# SCH_sign-language-translation-glove_2025.net
KiCad netlist of a schematic drawn in EasyEDA
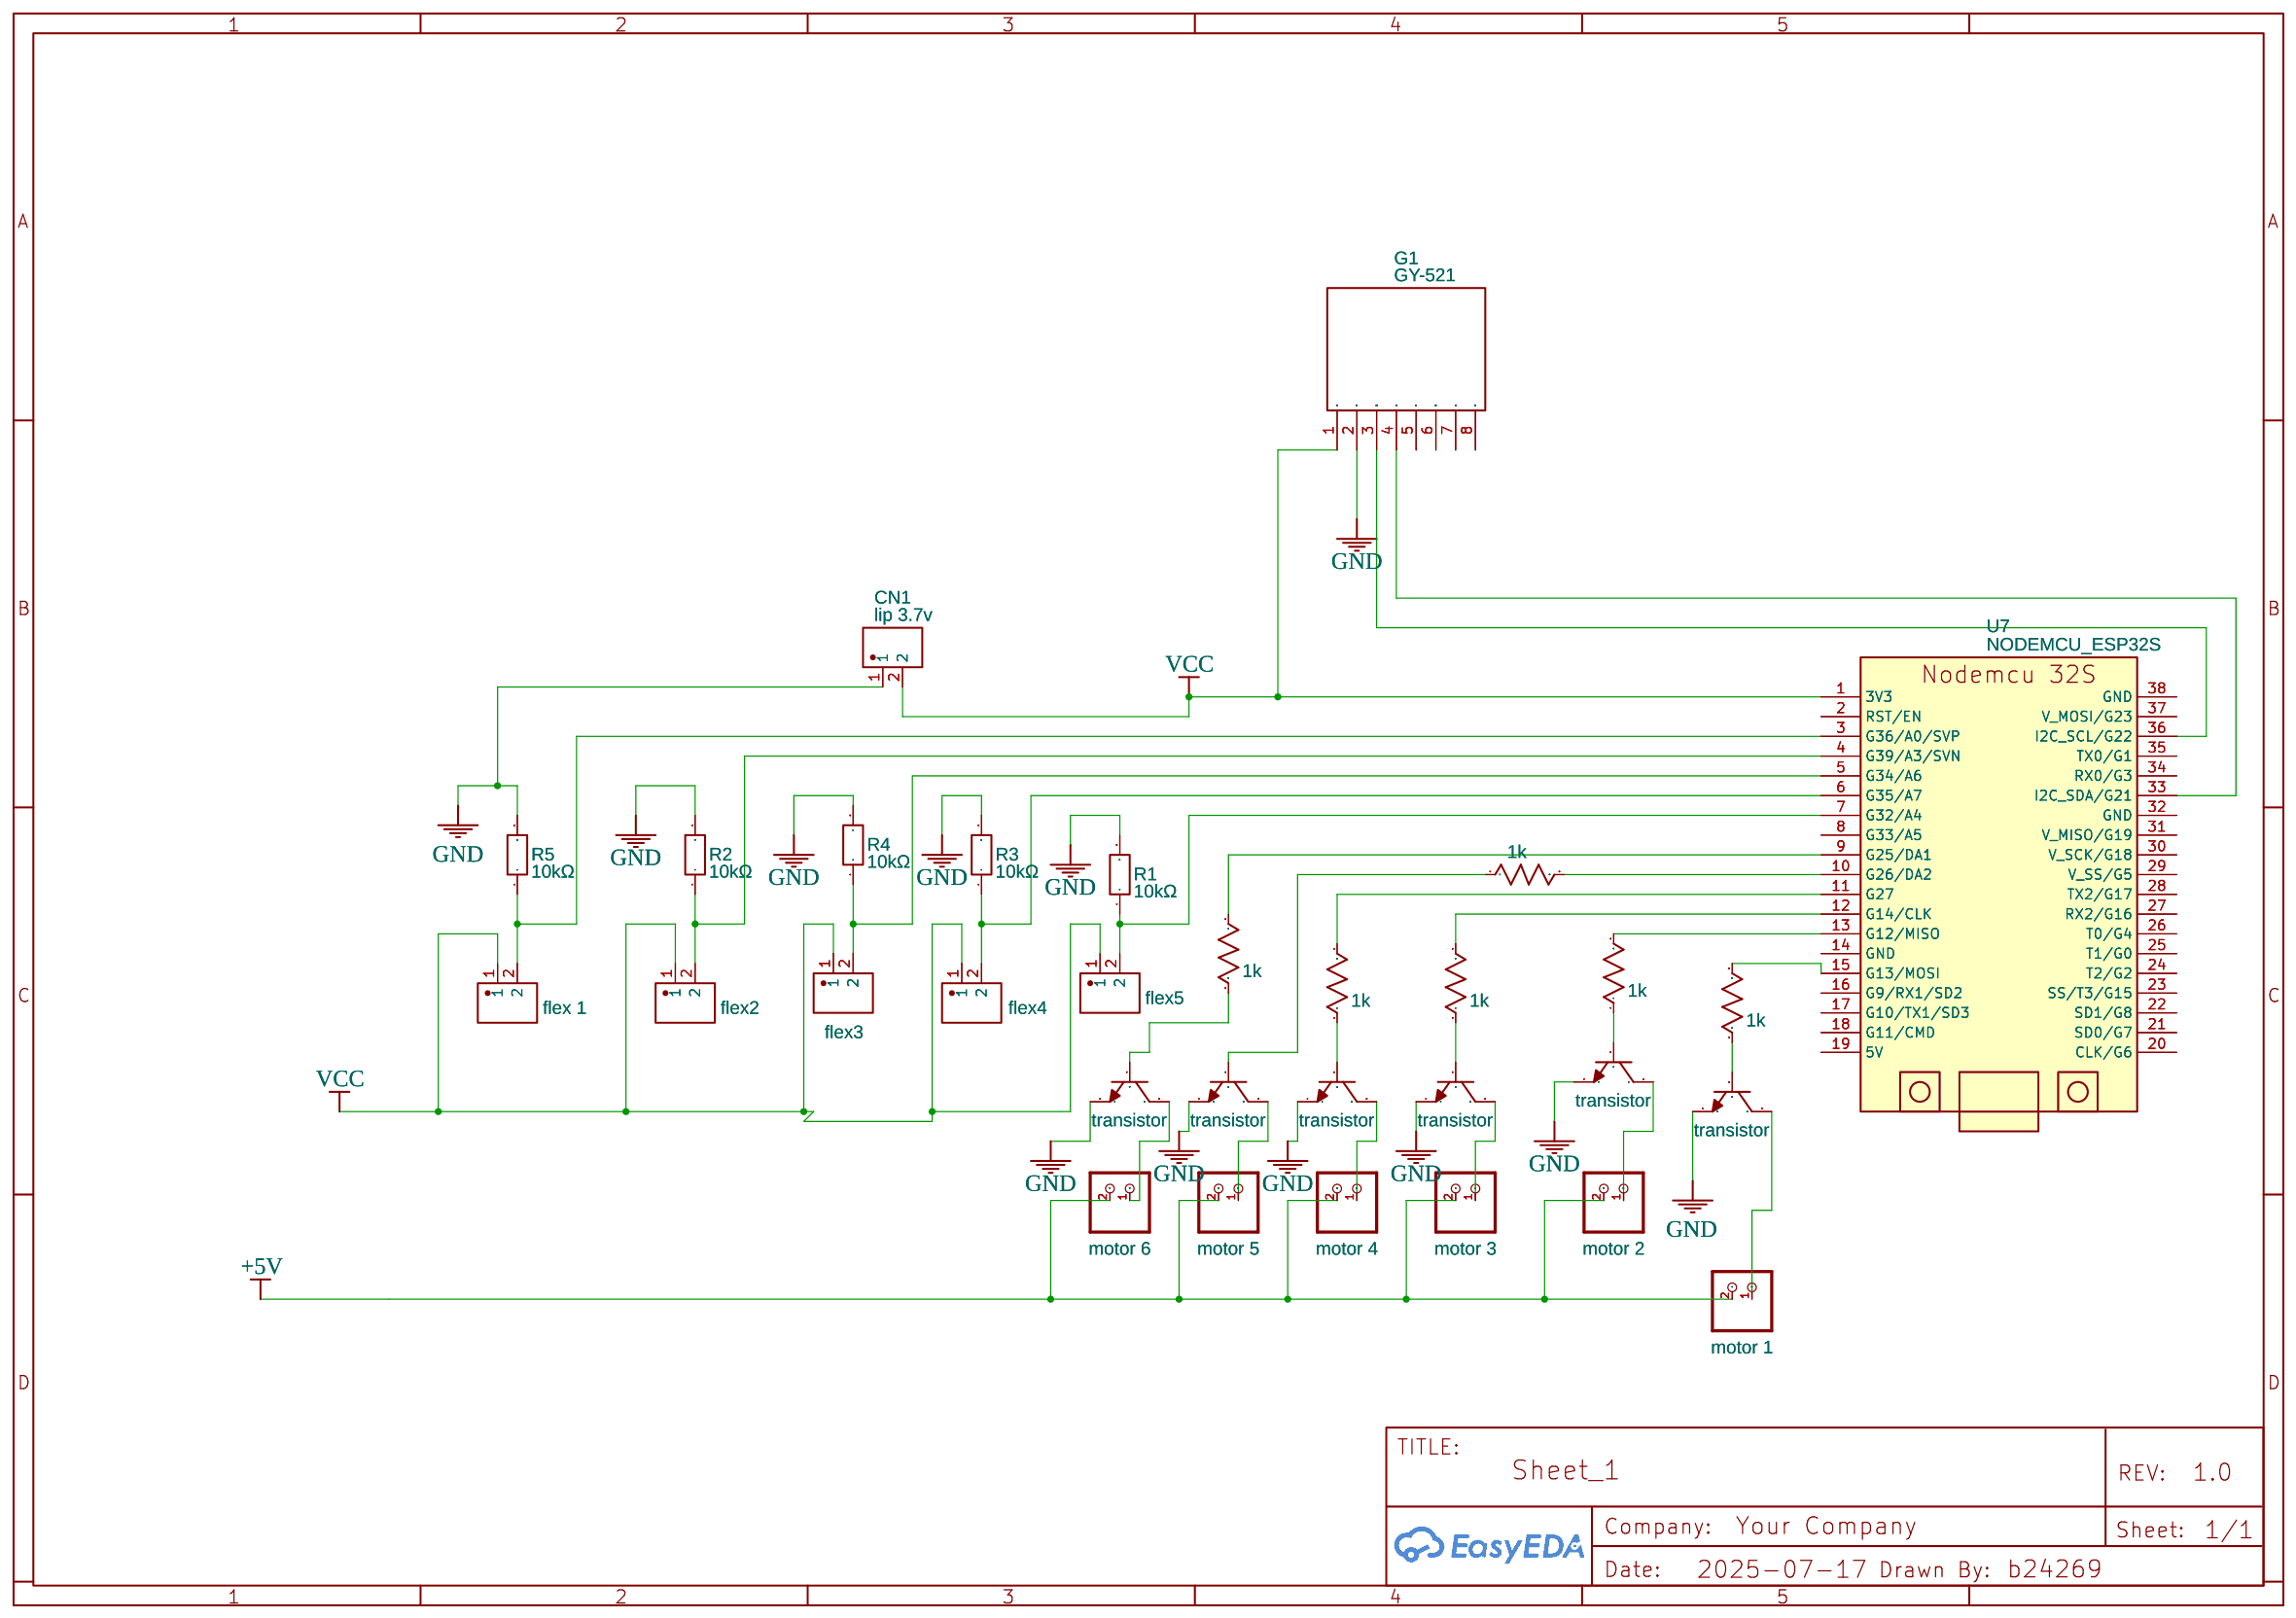
[diagram p0: schematic sheet]

(export (version "E")
  (design (tool "Eeschema 10.0.6"))
  (components
    (comp (ref "CN1")
      (value "lip 3.7v")
      (fields
        (field (name "Manufacturer Part") "2.0-2P ZZDK-R PCB Connector")
        (field (name "Manufacturer") "SHOU HAN(首韩)")
      )
      (libsource (lib "") (part "2.0-2P ZZDK-R PCB CONNECTOR"))
    )
    (comp (ref "CN2") (value "motor 1") (libsource (lib "") (part "JST_2PIN-THM")))
    (comp (ref "CN3") (value "motor 2") (libsource (lib "") (part "JST_2PIN-THM")))
    (comp (ref "CN4") (value "motor 3") (libsource (lib "") (part "JST_2PIN-THM")))
    (comp (ref "CN5") (value "motor 4") (libsource (lib "") (part "JST_2PIN-THM")))
    (comp (ref "CN6") (value "motor 5") (libsource (lib "") (part "JST_2PIN-THM")))
    (comp (ref "CN7") (value "motor 6") (libsource (lib "") (part "JST_2PIN-THM")))
    (comp (ref "G1") (value "GY-521") (libsource (lib "") (part "GY-521")))
    (comp (ref "Q1")
      (value "transistor")
      (fields (field (name "Manufacturer Part") "2n3904S-RTK/PS") (field (name "Manufacturer") "KEC"))
      (libsource (lib "") (part "2N3904(SOT-23)"))
    )
    (comp (ref "Q2")
      (value "transistor")
      (fields (field (name "Manufacturer Part") "2n3904S-RTK/PS") (field (name "Manufacturer") "KEC"))
      (libsource (lib "") (part "2N3904(SOT-23)"))
    )
    (comp (ref "Q3")
      (value "transistor")
      (fields (field (name "Manufacturer Part") "2n3904S-RTK/PS") (field (name "Manufacturer") "KEC"))
      (libsource (lib "") (part "2N3904(SOT-23)"))
    )
    (comp (ref "Q4")
      (value "transistor")
      (fields (field (name "Manufacturer Part") "2n3904S-RTK/PS") (field (name "Manufacturer") "KEC"))
      (libsource (lib "") (part "2N3904(SOT-23)"))
    )
    (comp (ref "Q5")
      (value "transistor")
      (fields (field (name "Manufacturer Part") "2n3904S-RTK/PS") (field (name "Manufacturer") "KEC"))
      (libsource (lib "") (part "2N3904(SOT-23)"))
    )
    (comp (ref "Q6")
      (value "transistor")
      (fields (field (name "Manufacturer Part") "2n3904S-RTK/PS") (field (name "Manufacturer") "KEC"))
      (libsource (lib "") (part "2N3904(SOT-23)"))
    )
    (comp (ref "R1")
      (value "10kΩ")
      (fields (field (name "Manufacturer Part") "APC0805T10K0Z") (field (name "Manufacturer") "Ohmite"))
      (libsource (lib "") (part "APC0805T10K0Z"))
    )
    (comp (ref "R2")
      (value "10kΩ")
      (fields (field (name "Manufacturer Part") "APC0805T10K0Z") (field (name "Manufacturer") "Ohmite"))
      (libsource (lib "") (part "APC0805T10K0Z"))
    )
    (comp (ref "R3")
      (value "10kΩ")
      (fields (field (name "Manufacturer Part") "APC0805T10K0Z") (field (name "Manufacturer") "Ohmite"))
      (libsource (lib "") (part "APC0805T10K0Z"))
    )
    (comp (ref "R4")
      (value "10kΩ")
      (fields (field (name "Manufacturer Part") "APC0805T10K0Z") (field (name "Manufacturer") "Ohmite"))
      (libsource (lib "") (part "APC0805T10K0Z"))
    )
    (comp (ref "R5")
      (value "10kΩ")
      (fields (field (name "Manufacturer Part") "APC0805T10K0Z") (field (name "Manufacturer") "Ohmite"))
      (libsource (lib "") (part "APC0805T10K0Z"))
    )
    (comp (ref "R6") (value "1k") (libsource (lib "") (part "R_0805_US")))
    (comp (ref "R7") (value "1k") (libsource (lib "") (part "R_0805_US")))
    (comp (ref "R8") (value "1k") (libsource (lib "") (part "R_0805_US")))
    (comp (ref "R9") (value "1k") (libsource (lib "") (part "R_0805_US")))
    (comp (ref "R10") (value "1k") (libsource (lib "") (part "R_0805_US_2")))
    (comp (ref "R11") (value "1k") (libsource (lib "") (part "R_0805_US_1")))
    (comp (ref "U1")
      (value "flex5")
      (fields
        (field (name "Manufacturer Part") "5BML8-11732-102-W0")
        (field (name "Manufacturer") "SAMZO(三佐)")
      )
      (libsource (lib "") (part "5BML8-11732-102-W0"))
    )
    (comp (ref "U2")
      (value "flex 1")
      (fields
        (field (name "Manufacturer Part") "5BML8-11732-102-W0")
        (field (name "Manufacturer") "SAMZO(三佐)")
      )
      (libsource (lib "") (part "5BML8-11732-102-W0"))
    )
    (comp (ref "U3")
      (value "flex2")
      (fields
        (field (name "Manufacturer Part") "5BML8-11732-102-W0")
        (field (name "Manufacturer") "SAMZO(三佐)")
      )
      (libsource (lib "") (part "5BML8-11732-102-W0"))
    )
    (comp (ref "U4")
      (value "flex3")
      (fields
        (field (name "Manufacturer Part") "5BML8-11732-102-W0")
        (field (name "Manufacturer") "SAMZO(三佐)")
      )
      (libsource (lib "") (part "5BML8-11732-102-W0"))
    )
    (comp (ref "U5")
      (value "flex4")
      (fields
        (field (name "Manufacturer Part") "5BML8-11732-102-W0")
        (field (name "Manufacturer") "SAMZO(三佐)")
      )
      (libsource (lib "") (part "5BML8-11732-102-W0"))
    )
    (comp (ref "U7")
      (value "NODEMCU_ESP32S")
      (fields (field (name "Manufacturer Part") "Nodemcu esp32"))
      (libsource (lib "") (part "NODEMCU_ESP32S"))
    )
  )
  (nets
    (net (code "1") (name "+5V") (class "Default")
      (node (ref "CN2") (pin "2") (pinfunction "1_2") (pintype "bidirectional"))
      (node (ref "CN3") (pin "2") (pinfunction "1_2") (pintype "bidirectional"))
      (node (ref "CN4") (pin "2") (pinfunction "1_2") (pintype "bidirectional"))
      (node (ref "CN5") (pin "2") (pinfunction "1_2") (pintype "bidirectional"))
      (node (ref "CN6") (pin "2") (pinfunction "1_2") (pintype "bidirectional"))
      (node (ref "CN7") (pin "2") (pinfunction "1_2") (pintype "bidirectional"))
    )
    (net (code "2") (name "GND") (class "Default")
      (node (ref "CN1") (pin "1") (pinfunction "1_1") (pintype "unspecified"))
      (node (ref "G1") (pin "2") (pinfunction "GND_2") (pintype "unspecified"))
      (node (ref "Q1") (pin "1") (pinfunction "E_1") (pintype "input"))
      (node (ref "Q2") (pin "1") (pinfunction "E_1") (pintype "input"))
      (node (ref "Q3") (pin "1") (pinfunction "E_1") (pintype "input"))
      (node (ref "Q4") (pin "1") (pinfunction "E_1") (pintype "input"))
      (node (ref "Q5") (pin "1") (pinfunction "E_1") (pintype "input"))
      (node (ref "Q6") (pin "1") (pinfunction "E_1") (pintype "input"))
      (node (ref "R1") (pin "2") (pinfunction "2_2") (pintype "unspecified"))
      (node (ref "R2") (pin "2") (pinfunction "2_2") (pintype "unspecified"))
      (node (ref "R3") (pin "2") (pinfunction "2_2") (pintype "unspecified"))
      (node (ref "R4") (pin "2") (pinfunction "2_2") (pintype "unspecified"))
      (node (ref "R5") (pin "2") (pinfunction "2_2") (pintype "unspecified"))
    )
    (net (code "3") (name "Net-(CN2-2)") (class "Default")
      (node (ref "CN2") (pin "1") (pinfunction "2_1") (pintype "bidirectional"))
      (node (ref "Q1") (pin "3") (pinfunction "C_3") (pintype "input"))
    )
    (net (code "4") (name "Net-(CN3-2)") (class "Default")
      (node (ref "CN3") (pin "1") (pinfunction "2_1") (pintype "bidirectional"))
      (node (ref "Q2") (pin "3") (pinfunction "C_3") (pintype "input"))
    )
    (net (code "5") (name "Net-(CN4-2)") (class "Default")
      (node (ref "CN4") (pin "1") (pinfunction "2_1") (pintype "bidirectional"))
      (node (ref "Q3") (pin "3") (pinfunction "C_3") (pintype "input"))
    )
    (net (code "6") (name "Net-(CN5-2)") (class "Default")
      (node (ref "CN5") (pin "1") (pinfunction "2_1") (pintype "bidirectional"))
      (node (ref "Q4") (pin "3") (pinfunction "C_3") (pintype "input"))
    )
    (net (code "7") (name "Net-(CN6-2)") (class "Default")
      (node (ref "CN6") (pin "1") (pinfunction "2_1") (pintype "bidirectional"))
      (node (ref "Q5") (pin "3") (pinfunction "C_3") (pintype "input"))
    )
    (net (code "8") (name "Net-(CN7-2)") (class "Default")
      (node (ref "CN7") (pin "1") (pinfunction "2_1") (pintype "bidirectional"))
      (node (ref "Q6") (pin "3") (pinfunction "C_3") (pintype "input"))
    )
    (net (code "9") (name "Net-(G1-SCL)") (class "Default")
      (node (ref "G1") (pin "3") (pinfunction "SCL_3") (pintype "unspecified"))
      (node (ref "U7") (pin "36") (pinfunction "I2C_SCL/G22_36") (pintype "bidirectional"))
    )
    (net (code "10") (name "Net-(G1-SDA)") (class "Default")
      (node (ref "G1") (pin "4") (pinfunction "SDA_4") (pintype "unspecified"))
      (node (ref "U7") (pin "33") (pinfunction "I2C_SDA/G21_33") (pintype "bidirectional"))
    )
    (net (code "11") (name "Net-(Q1-B)") (class "Default")
      (node (ref "Q1") (pin "2") (pinfunction "B_2") (pintype "input"))
      (node (ref "R6") (pin "1") (pinfunction "1_1") (pintype "unspecified"))
    )
    (net (code "12") (name "Net-(Q2-B)") (class "Default")
      (node (ref "Q2") (pin "2") (pinfunction "B_2") (pintype "input"))
      (node (ref "R7") (pin "1") (pinfunction "1_1") (pintype "unspecified"))
    )
    (net (code "13") (name "Net-(Q3-B)") (class "Default")
      (node (ref "Q3") (pin "2") (pinfunction "B_2") (pintype "input"))
      (node (ref "R8") (pin "1") (pinfunction "1_1") (pintype "unspecified"))
    )
    (net (code "14") (name "Net-(Q4-B)") (class "Default")
      (node (ref "Q4") (pin "2") (pinfunction "B_2") (pintype "input"))
      (node (ref "R9") (pin "1") (pinfunction "1_1") (pintype "unspecified"))
    )
    (net (code "15") (name "Net-(Q5-B)") (class "Default")
      (node (ref "Q5") (pin "2") (pinfunction "B_2") (pintype "input"))
      (node (ref "R10") (pin "1") (pinfunction "1_1") (pintype "unspecified"))
    )
    (net (code "16") (name "Net-(Q6-B)") (class "Default")
      (node (ref "Q6") (pin "2") (pinfunction "B_2") (pintype "input"))
      (node (ref "R11") (pin "2") (pinfunction "2_2") (pintype "unspecified"))
    )
    (net (code "17") (name "Net-(U7-G12{slash}MISO)") (class "Default")
      (node (ref "R7") (pin "2") (pinfunction "2_2") (pintype "unspecified"))
      (node (ref "U7") (pin "13") (pinfunction "G12/MISO_13") (pintype "bidirectional"))
    )
    (net (code "18") (name "Net-(U7-G13{slash}MOSI)") (class "Default")
      (node (ref "R6") (pin "2") (pinfunction "2_2") (pintype "unspecified"))
      (node (ref "U7") (pin "15") (pinfunction "G13/MOSI_15") (pintype "bidirectional"))
    )
    (net (code "19") (name "Net-(U7-G14{slash}CLK)") (class "Default")
      (node (ref "R8") (pin "2") (pinfunction "2_2") (pintype "unspecified"))
      (node (ref "U7") (pin "12") (pinfunction "G14/CLK_12") (pintype "bidirectional"))
    )
    (net (code "20") (name "Net-(U7-G25{slash}DA1)") (class "Default")
      (node (ref "R11") (pin "1") (pinfunction "1_1") (pintype "unspecified"))
      (node (ref "U7") (pin "9") (pinfunction "G25/DA1_9") (pintype "bidirectional"))
    )
    (net (code "21") (name "Net-(U7-G26{slash}DA2)") (class "Default")
      (node (ref "R10") (pin "2") (pinfunction "2_2") (pintype "unspecified"))
      (node (ref "U7") (pin "10") (pinfunction "G26/DA2_10") (pintype "bidirectional"))
    )
    (net (code "22") (name "Net-(U7-G27)") (class "Default")
      (node (ref "R9") (pin "2") (pinfunction "2_2") (pintype "unspecified"))
      (node (ref "U7") (pin "11") (pinfunction "G27_11") (pintype "bidirectional"))
    )
    (net (code "23") (name "Net-(U7-G32{slash}A4)") (class "Default")
      (node (ref "R1") (pin "1") (pinfunction "1_1") (pintype "unspecified"))
      (node (ref "U1") (pin "2") (pinfunction "2_2") (pintype "unspecified"))
      (node (ref "U7") (pin "7") (pinfunction "G32/A4_7") (pintype "bidirectional"))
    )
    (net (code "24") (name "Net-(U7-G34{slash}A6)") (class "Default")
      (node (ref "R4") (pin "1") (pinfunction "1_1") (pintype "unspecified"))
      (node (ref "U4") (pin "2") (pinfunction "2_2") (pintype "unspecified"))
      (node (ref "U7") (pin "5") (pinfunction "G34/A6_5") (pintype "bidirectional"))
    )
    (net (code "25") (name "Net-(U7-G35{slash}A7)") (class "Default")
      (node (ref "R3") (pin "1") (pinfunction "1_1") (pintype "unspecified"))
      (node (ref "U5") (pin "2") (pinfunction "2_2") (pintype "unspecified"))
      (node (ref "U7") (pin "6") (pinfunction "G35/A7_6") (pintype "bidirectional"))
    )
    (net (code "26") (name "Net-(U7-G36{slash}A0{slash}SVP)") (class "Default")
      (node (ref "R5") (pin "1") (pinfunction "1_1") (pintype "unspecified"))
      (node (ref "U2") (pin "2") (pinfunction "2_2") (pintype "unspecified"))
      (node (ref "U7") (pin "3") (pinfunction "G36/A0/SVP_3") (pintype "bidirectional"))
    )
    (net (code "27") (name "Net-(U7-G39{slash}A3{slash}SVN)") (class "Default")
      (node (ref "R2") (pin "1") (pinfunction "1_1") (pintype "unspecified"))
      (node (ref "U3") (pin "2") (pinfunction "2_2") (pintype "unspecified"))
      (node (ref "U7") (pin "4") (pinfunction "G39/A3/SVN_4") (pintype "bidirectional"))
    )
    (net (code "28") (name "VCC") (class "Default")
      (node (ref "CN1") (pin "2") (pinfunction "2_2") (pintype "unspecified"))
      (node (ref "G1") (pin "1") (pinfunction "VCC_1") (pintype "unspecified"))
      (node (ref "U1") (pin "1") (pinfunction "1_1") (pintype "unspecified"))
      (node (ref "U2") (pin "1") (pinfunction "1_1") (pintype "unspecified"))
      (node (ref "U3") (pin "1") (pinfunction "1_1") (pintype "unspecified"))
      (node (ref "U4") (pin "1") (pinfunction "1_1") (pintype "unspecified"))
      (node (ref "U5") (pin "1") (pinfunction "1_1") (pintype "unspecified"))
      (node (ref "U7") (pin "1") (pinfunction "3V3_1") (pintype "passive"))
    )
    (net (code "29") (name "unconnected-(G1-AD0-Pad7)") (class "Default")
      (node (ref "G1") (pin "7") (pinfunction "AD0_7") (pintype "unspecified"))
    )
    (net (code "30") (name "unconnected-(G1-INT-Pad8)") (class "Default")
      (node (ref "G1") (pin "8") (pinfunction "INT_8") (pintype "unspecified"))
    )
    (net (code "31") (name "unconnected-(G1-XCL-Pad6)") (class "Default")
      (node (ref "G1") (pin "6") (pinfunction "XCL_6") (pintype "unspecified"))
    )
    (net (code "32") (name "unconnected-(G1-XDA-Pad5)") (class "Default")
      (node (ref "G1") (pin "5") (pinfunction "XDA_5") (pintype "unspecified"))
    )
    (net (code "33") (name "unconnected-(U7-5V-Pad19)") (class "Default")
      (node (ref "U7") (pin "19") (pinfunction "5V_19") (pintype "passive"))
    )
    (net (code "34") (name "unconnected-(U7-CLK{slash}G6-Pad20)") (class "Default")
      (node (ref "U7") (pin "20") (pinfunction "CLK/G6_20") (pintype "bidirectional"))
    )
    (net (code "35") (name "unconnected-(U7-G9{slash}RX1{slash}SD2-Pad16)") (class "Default")
      (node (ref "U7") (pin "16") (pinfunction "G9/RX1/SD2_16") (pintype "bidirectional"))
    )
    (net (code "36") (name "unconnected-(U7-G10{slash}TX1{slash}SD3-Pad17)") (class "Default")
      (node (ref "U7") (pin "17") (pinfunction "G10/TX1/SD3_17") (pintype "bidirectional"))
    )
    (net (code "37") (name "unconnected-(U7-G11{slash}CMD-Pad18)") (class "Default")
      (node (ref "U7") (pin "18") (pinfunction "G11/CMD_18") (pintype "bidirectional"))
    )
    (net (code "38") (name "unconnected-(U7-G33{slash}A5-Pad8)") (class "Default")
      (node (ref "U7") (pin "8") (pinfunction "G33/A5_8") (pintype "bidirectional"))
    )
    (net (code "39") (name "unconnected-(U7-GND-Pad14)") (class "Default")
      (node (ref "U7") (pin "14") (pinfunction "GND_14") (pintype "passive"))
    )
    (net (code "40") (name "unconnected-(U7-GND-Pad32)") (class "Default")
      (node (ref "U7") (pin "32") (pinfunction "GND_32") (pintype "passive"))
    )
    (net (code "41") (name "unconnected-(U7-GND-Pad38)") (class "Default")
      (node (ref "U7") (pin "38") (pinfunction "GND_38") (pintype "passive"))
    )
    (net (code "42") (name "unconnected-(U7-RST{slash}EN-Pad2)") (class "Default")
      (node (ref "U7") (pin "2") (pinfunction "RST/EN_2") (pintype "bidirectional"))
    )
    (net (code "43") (name "unconnected-(U7-RX0{slash}G3-Pad34)") (class "Default")
      (node (ref "U7") (pin "34") (pinfunction "RX0/G3_34") (pintype "bidirectional"))
    )
    (net (code "44") (name "unconnected-(U7-RX2{slash}G16-Pad27)") (class "Default")
      (node (ref "U7") (pin "27") (pinfunction "RX2/G16_27") (pintype "bidirectional"))
    )
    (net (code "45") (name "unconnected-(U7-SD0{slash}G7-Pad21)") (class "Default")
      (node (ref "U7") (pin "21") (pinfunction "SD0/G7_21") (pintype "bidirectional"))
    )
    (net (code "46") (name "unconnected-(U7-SD1{slash}G8-Pad22)") (class "Default")
      (node (ref "U7") (pin "22") (pinfunction "SD1/G8_22") (pintype "bidirectional"))
    )
    (net (code "47") (name "unconnected-(U7-SS{slash}T3{slash}G15-Pad23)") (class "Default")
      (node (ref "U7") (pin "23") (pinfunction "SS/T3/G15_23") (pintype "bidirectional"))
    )
    (net (code "48") (name "unconnected-(U7-T0{slash}G4-Pad26)") (class "Default")
      (node (ref "U7") (pin "26") (pinfunction "T0/G4_26") (pintype "bidirectional"))
    )
    (net (code "49") (name "unconnected-(U7-T1{slash}G0-Pad25)") (class "Default")
      (node (ref "U7") (pin "25") (pinfunction "T1/G0_25") (pintype "bidirectional"))
    )
    (net (code "50") (name "unconnected-(U7-T2{slash}G2-Pad24)") (class "Default")
      (node (ref "U7") (pin "24") (pinfunction "T2/G2_24") (pintype "bidirectional"))
    )
    (net (code "51") (name "unconnected-(U7-TX0{slash}G1-Pad35)") (class "Default")
      (node (ref "U7") (pin "35") (pinfunction "TX0/G1_35") (pintype "bidirectional"))
    )
    (net (code "52") (name "unconnected-(U7-TX2{slash}G17-Pad28)") (class "Default")
      (node (ref "U7") (pin "28") (pinfunction "TX2/G17_28") (pintype "bidirectional"))
    )
    (net (code "53") (name "unconnected-(U7-V_MISO{slash}G19-Pad31)") (class "Default")
      (node (ref "U7") (pin "31") (pinfunction "V_MISO/G19_31") (pintype "bidirectional"))
    )
    (net (code "54") (name "unconnected-(U7-V_MOSI{slash}G23-Pad37)") (class "Default")
      (node (ref "U7") (pin "37") (pinfunction "V_MOSI/G23_37") (pintype "bidirectional"))
    )
    (net (code "55") (name "unconnected-(U7-V_SCK{slash}G18-Pad30)") (class "Default")
      (node (ref "U7") (pin "30") (pinfunction "V_SCK/G18_30") (pintype "bidirectional"))
    )
    (net (code "56") (name "unconnected-(U7-V_SS{slash}G5-Pad29)") (class "Default")
      (node (ref "U7") (pin "29") (pinfunction "V_SS/G5_29") (pintype "bidirectional"))
    )
  )
)
